# das_updated_v7.net
KiCad netlist of a schematic drawn in EAGLE
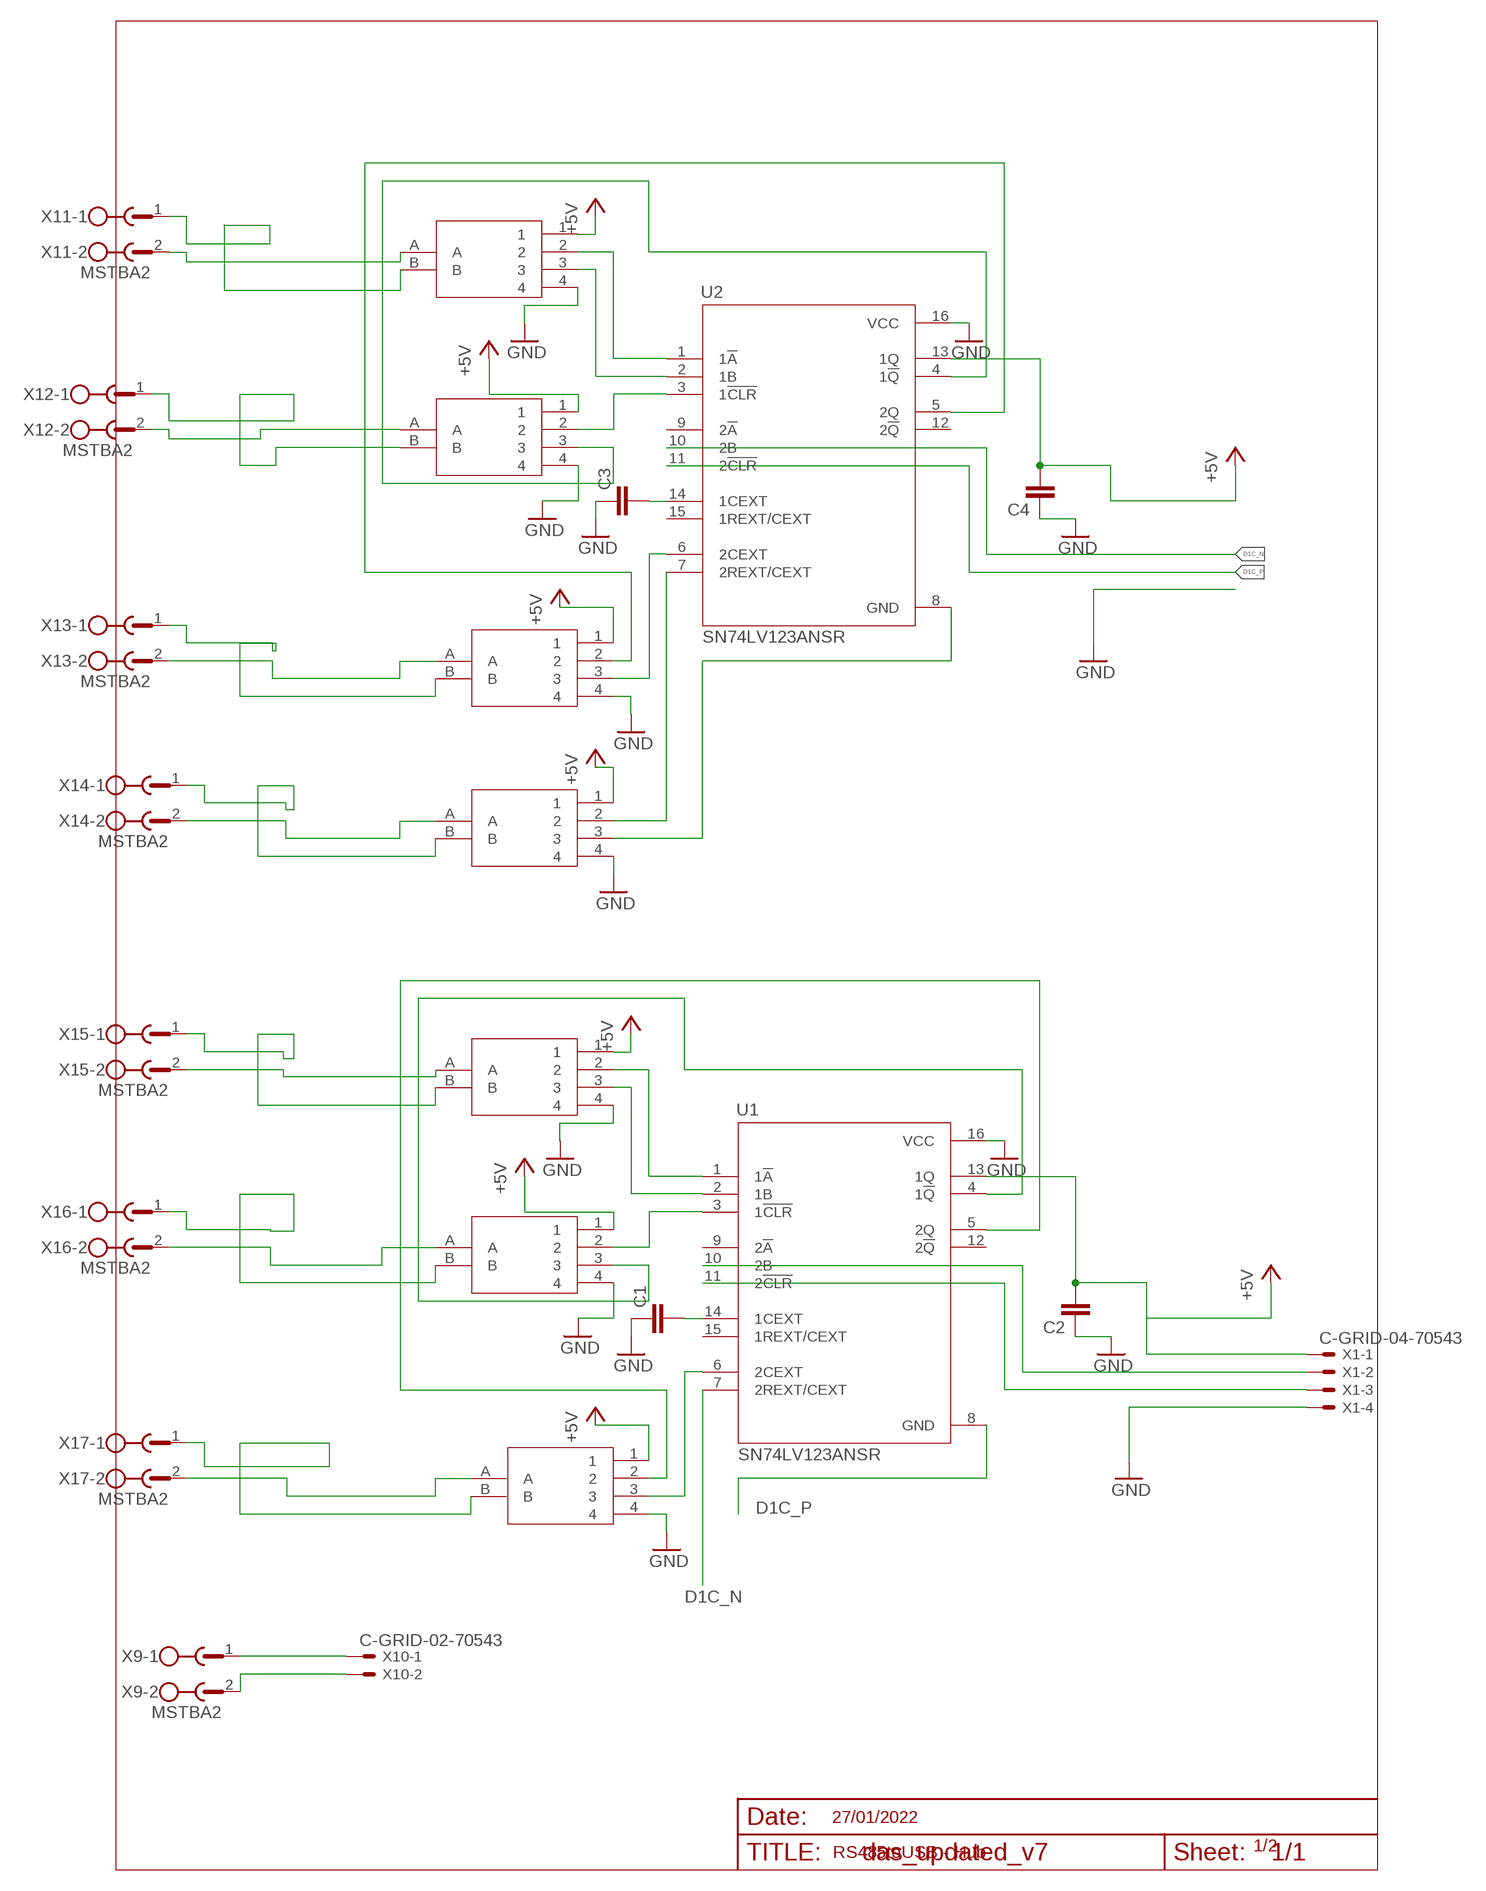
[diagram p0: schematic, sheet 1]

(export (version "E")
  (design (tool "Eeschema 10.0.6"))
  (components
    (comp (ref "C1")
      (value "C-EUC0603K")
      (footprint "eagle-import:C0603K")
      (libsource (lib "eagle-import") (part "C-EUC0603K"))
    )
    (comp (ref "C2")
      (value "C-EUC0603K")
      (footprint "eagle-import:C0603K")
      (libsource (lib "eagle-import") (part "C-EUC0603K"))
    )
    (comp (ref "C3")
      (value "C-EUC0603K")
      (footprint "eagle-import:C0603K")
      (libsource (lib "eagle-import") (part "C-EUC0603K"))
    )
    (comp (ref "C4")
      (value "C-EUC0603K")
      (footprint "eagle-import:C0603K")
      (libsource (lib "eagle-import") (part "C-EUC0603K"))
    )
    (comp (ref "U1")
      (value "SN74LV123ANSR")
      (footprint "eagle-import:SOIC127P780X200-16N")
      (fields (field (name "MF") "Texas Instruments"))
      (libsource (lib "eagle-import") (part "SN74LV123ANSR"))
    )
    (comp (ref "U2")
      (value "SN74LV123ANSR")
      (footprint "eagle-import:SOIC127P780X200-16N")
      (fields (field (name "MF") "Texas Instruments"))
      (libsource (lib "eagle-import") (part "SN74LV123ANSR"))
    )
    (comp (ref "USB2RS1")
      (value "USB2RS485")
      (footprint "eagle-import:USB2RS485")
      (libsource (lib "eagle-import") (part "USB2RS485"))
    )
    (comp (ref "USB2RS2")
      (value "USB2RS485")
      (footprint "eagle-import:USB2RS485")
      (libsource (lib "eagle-import") (part "USB2RS485"))
    )
    (comp (ref "USB2RS3")
      (value "USB2RS485")
      (footprint "eagle-import:USB2RS485")
      (libsource (lib "eagle-import") (part "USB2RS485"))
    )
    (comp (ref "USB2RS5")
      (value "USB2RS485")
      (footprint "eagle-import:USB2RS485")
      (libsource (lib "eagle-import") (part "USB2RS485"))
    )
    (comp (ref "USB2RS6")
      (value "USB2RS485")
      (footprint "eagle-import:USB2RS485")
      (libsource (lib "eagle-import") (part "USB2RS485"))
    )
    (comp (ref "USB2RS7")
      (value "USB2RS485")
      (footprint "eagle-import:USB2RS485")
      (libsource (lib "eagle-import") (part "USB2RS485"))
    )
    (comp (ref "USB2RS8")
      (value "USB2RS485")
      (footprint "eagle-import:USB2RS485")
      (libsource (lib "eagle-import") (part "USB2RS485"))
    )
    (comp (ref "X1")
      (value "C-GRID-04-70543")
      (footprint "eagle-import:70543-04")
      (fields (field (name "MF") "MOLEX"))
      (libsource (lib "eagle-import") (part "C-GRID-04-70543"))
    )
    (comp (ref "X9")
      (value "MSTBA2")
      (footprint "eagle-import:MSTBA2")
      (fields (field (name "MF") "FARNELL") (field (name "MPN") "1757242"))
      (libsource (lib "eagle-import") (part "MSTBA2"))
    )
    (comp (ref "X10")
      (value "C-GRID-02-70543")
      (footprint "eagle-import:70543-02")
      (fields (field (name "MF") "MOLEX"))
      (libsource (lib "eagle-import") (part "C-GRID-02-70543"))
    )
    (comp (ref "X11")
      (value "MSTBA2")
      (footprint "eagle-import:MSTBA2")
      (fields (field (name "MF") "FARNELL") (field (name "MPN") "1757242"))
      (libsource (lib "eagle-import") (part "MSTBA2"))
    )
    (comp (ref "X12")
      (value "MSTBA2")
      (footprint "eagle-import:MSTBA2")
      (fields (field (name "MF") "FARNELL") (field (name "MPN") "1757242"))
      (libsource (lib "eagle-import") (part "MSTBA2"))
    )
    (comp (ref "X13")
      (value "MSTBA2")
      (footprint "eagle-import:MSTBA2")
      (fields (field (name "MF") "FARNELL") (field (name "MPN") "1757242"))
      (libsource (lib "eagle-import") (part "MSTBA2"))
    )
    (comp (ref "X14")
      (value "MSTBA2")
      (footprint "eagle-import:MSTBA2")
      (fields (field (name "MF") "FARNELL") (field (name "MPN") "1757242"))
      (libsource (lib "eagle-import") (part "MSTBA2"))
    )
    (comp (ref "X15")
      (value "MSTBA2")
      (footprint "eagle-import:MSTBA2")
      (fields (field (name "MF") "FARNELL") (field (name "MPN") "1757242"))
      (libsource (lib "eagle-import") (part "MSTBA2"))
    )
    (comp (ref "X16")
      (value "MSTBA2")
      (footprint "eagle-import:MSTBA2")
      (fields (field (name "MF") "FARNELL") (field (name "MPN") "1757242"))
      (libsource (lib "eagle-import") (part "MSTBA2"))
    )
    (comp (ref "X17")
      (value "MSTBA2")
      (footprint "eagle-import:MSTBA2")
      (fields (field (name "MF") "FARNELL") (field (name "MPN") "1757242"))
      (libsource (lib "eagle-import") (part "MSTBA2"))
    )
  )
  (nets
    (net (code "1") (name "+5V") (class "Default")
      (node (ref "C2") (pin "2") (pinfunction "2_2") (pintype "passive"))
      (node (ref "C4") (pin "2") (pinfunction "2_2") (pintype "passive"))
      (node (ref "U1") (pin "13") (pinfunction "1Q_13") (pintype "output"))
      (node (ref "U2") (pin "13") (pinfunction "1Q_13") (pintype "output"))
      (node (ref "USB2RS1") (pin "1") (pinfunction "1_1") (pintype "bidirectional"))
      (node (ref "USB2RS2") (pin "1") (pinfunction "1_1") (pintype "bidirectional"))
      (node (ref "USB2RS3") (pin "1") (pinfunction "1_1") (pintype "bidirectional"))
      (node (ref "USB2RS5") (pin "1") (pinfunction "1_1") (pintype "bidirectional"))
      (node (ref "USB2RS6") (pin "1") (pinfunction "1_1") (pintype "bidirectional"))
      (node (ref "USB2RS7") (pin "1") (pinfunction "1_1") (pintype "bidirectional"))
      (node (ref "USB2RS8") (pin "1") (pinfunction "1_1") (pintype "bidirectional"))
      (node (ref "X1") (pin "1") (pinfunction "S_1") (pintype "passive"))
    )
    (net (code "2") (name "D1C_N") (class "Default")
      (node (ref "U1") (pin "7") (pinfunction "2REXT/CEXT_7") (pintype "bidirectional"))
      (node (ref "U2") (pin "10") (pinfunction "2B_10") (pintype "input"))
    )
    (net (code "3") (name "D1C_P") (class "Default")
      (node (ref "U1") (pin "8") (pinfunction "GND_8") (pintype "power_in"))
      (node (ref "U2") (pin "11") (pinfunction "2~{CLR}_11") (pintype "input"))
    )
    (net (code "4") (name "GND") (class "Default")
      (node (ref "C1") (pin "1") (pinfunction "1_1") (pintype "passive"))
      (node (ref "C2") (pin "1") (pinfunction "1_1") (pintype "passive"))
      (node (ref "C3") (pin "1") (pinfunction "1_1") (pintype "passive"))
      (node (ref "C4") (pin "1") (pinfunction "1_1") (pintype "passive"))
      (node (ref "U1") (pin "16") (pinfunction "VCC_16") (pintype "power_in"))
      (node (ref "U2") (pin "16") (pinfunction "VCC_16") (pintype "power_in"))
      (node (ref "USB2RS1") (pin "4") (pinfunction "4_4") (pintype "bidirectional"))
      (node (ref "USB2RS2") (pin "4") (pinfunction "4_4") (pintype "bidirectional"))
      (node (ref "USB2RS3") (pin "4") (pinfunction "4_4") (pintype "bidirectional"))
      (node (ref "USB2RS5") (pin "4") (pinfunction "4_4") (pintype "bidirectional"))
      (node (ref "USB2RS6") (pin "4") (pinfunction "4_4") (pintype "bidirectional"))
      (node (ref "USB2RS7") (pin "4") (pinfunction "4_4") (pintype "bidirectional"))
      (node (ref "USB2RS8") (pin "4") (pinfunction "4_4") (pintype "bidirectional"))
      (node (ref "X1") (pin "4") (pinfunction "S_4") (pintype "passive"))
    )
    (net (code "5") (name "Net-(U1-1B)") (class "Default")
      (node (ref "U1") (pin "2") (pinfunction "1B_2") (pintype "input"))
      (node (ref "USB2RS1") (pin "3") (pinfunction "3_3") (pintype "bidirectional"))
    )
    (net (code "6") (name "Net-(U1-1CEXT)") (class "Default")
      (node (ref "C1") (pin "2") (pinfunction "2_2") (pintype "passive"))
      (node (ref "U1") (pin "14") (pinfunction "1CEXT_14") (pintype "bidirectional"))
    )
    (net (code "7") (name "Net-(U1-1~{A})") (class "Default")
      (node (ref "U1") (pin "1") (pinfunction "1~{A}_1") (pintype "input"))
      (node (ref "USB2RS1") (pin "2") (pinfunction "2_2") (pintype "bidirectional"))
    )
    (net (code "8") (name "Net-(U1-1~{CLR})") (class "Default")
      (node (ref "U1") (pin "3") (pinfunction "1~{CLR}_3") (pintype "input"))
      (node (ref "USB2RS2") (pin "2") (pinfunction "2_2") (pintype "bidirectional"))
    )
    (net (code "9") (name "Net-(U1-1~{Q})") (class "Default")
      (node (ref "U1") (pin "4") (pinfunction "1~{Q}_4") (pintype "output"))
      (node (ref "USB2RS2") (pin "3") (pinfunction "3_3") (pintype "bidirectional"))
    )
    (net (code "10") (name "Net-(U1-2B)") (class "Default")
      (node (ref "U1") (pin "10") (pinfunction "2B_10") (pintype "input"))
      (node (ref "X1") (pin "2") (pinfunction "S_2") (pintype "passive"))
    )
    (net (code "11") (name "Net-(U1-2CEXT)") (class "Default")
      (node (ref "U1") (pin "6") (pinfunction "2CEXT_6") (pintype "bidirectional"))
      (node (ref "USB2RS3") (pin "3") (pinfunction "3_3") (pintype "bidirectional"))
    )
    (net (code "12") (name "Net-(U1-2Q)") (class "Default")
      (node (ref "U1") (pin "5") (pinfunction "2Q_5") (pintype "output"))
      (node (ref "USB2RS3") (pin "2") (pinfunction "2_2") (pintype "bidirectional"))
    )
    (net (code "13") (name "Net-(U1-2~{CLR})") (class "Default")
      (node (ref "U1") (pin "11") (pinfunction "2~{CLR}_11") (pintype "input"))
      (node (ref "X1") (pin "3") (pinfunction "S_3") (pintype "passive"))
    )
    (net (code "14") (name "Net-(U2-1B)") (class "Default")
      (node (ref "U2") (pin "2") (pinfunction "1B_2") (pintype "input"))
      (node (ref "USB2RS5") (pin "3") (pinfunction "3_3") (pintype "bidirectional"))
    )
    (net (code "15") (name "Net-(U2-1CEXT)") (class "Default")
      (node (ref "C3") (pin "2") (pinfunction "2_2") (pintype "passive"))
      (node (ref "U2") (pin "14") (pinfunction "1CEXT_14") (pintype "bidirectional"))
    )
    (net (code "16") (name "Net-(U2-1~{A})") (class "Default")
      (node (ref "U2") (pin "1") (pinfunction "1~{A}_1") (pintype "input"))
      (node (ref "USB2RS5") (pin "2") (pinfunction "2_2") (pintype "bidirectional"))
    )
    (net (code "17") (name "Net-(U2-1~{CLR})") (class "Default")
      (node (ref "U2") (pin "3") (pinfunction "1~{CLR}_3") (pintype "input"))
      (node (ref "USB2RS6") (pin "2") (pinfunction "2_2") (pintype "bidirectional"))
    )
    (net (code "18") (name "Net-(U2-1~{Q})") (class "Default")
      (node (ref "U2") (pin "4") (pinfunction "1~{Q}_4") (pintype "output"))
      (node (ref "USB2RS6") (pin "3") (pinfunction "3_3") (pintype "bidirectional"))
    )
    (net (code "19") (name "Net-(U2-2CEXT)") (class "Default")
      (node (ref "U2") (pin "6") (pinfunction "2CEXT_6") (pintype "bidirectional"))
      (node (ref "USB2RS7") (pin "3") (pinfunction "3_3") (pintype "bidirectional"))
    )
    (net (code "20") (name "Net-(U2-2Q)") (class "Default")
      (node (ref "U2") (pin "5") (pinfunction "2Q_5") (pintype "output"))
      (node (ref "USB2RS7") (pin "2") (pinfunction "2_2") (pintype "bidirectional"))
    )
    (net (code "21") (name "Net-(U2-2REXT{slash}CEXT)") (class "Default")
      (node (ref "U2") (pin "7") (pinfunction "2REXT/CEXT_7") (pintype "bidirectional"))
      (node (ref "USB2RS8") (pin "2") (pinfunction "2_2") (pintype "bidirectional"))
    )
    (net (code "22") (name "Net-(U2-GND)") (class "Default")
      (node (ref "U2") (pin "8") (pinfunction "GND_8") (pintype "power_in"))
      (node (ref "USB2RS8") (pin "3") (pinfunction "3_3") (pintype "bidirectional"))
    )
    (net (code "23") (name "Net-(USB2RS1-PadB)") (class "Default")
      (node (ref "USB2RS1") (pin "B") (pinfunction "B_B") (pintype "bidirectional"))
      (node (ref "X15") (pin "1") (pinfunction "1_1") (pintype "passive"))
    )
    (net (code "24") (name "Net-(USB2RS2-PadB)") (class "Default")
      (node (ref "USB2RS2") (pin "B") (pinfunction "B_B") (pintype "bidirectional"))
      (node (ref "X16") (pin "1") (pinfunction "1_1") (pintype "passive"))
    )
    (net (code "25") (name "Net-(USB2RS3-PadB)") (class "Default")
      (node (ref "USB2RS3") (pin "B") (pinfunction "B_B") (pintype "bidirectional"))
      (node (ref "X17") (pin "1") (pinfunction "1_1") (pintype "passive"))
    )
    (net (code "26") (name "Net-(USB2RS5-PadB)") (class "Default")
      (node (ref "USB2RS5") (pin "B") (pinfunction "B_B") (pintype "bidirectional"))
      (node (ref "X11") (pin "1") (pinfunction "1_1") (pintype "passive"))
    )
    (net (code "27") (name "Net-(USB2RS6-PadB)") (class "Default")
      (node (ref "USB2RS6") (pin "B") (pinfunction "B_B") (pintype "bidirectional"))
      (node (ref "X12") (pin "1") (pinfunction "1_1") (pintype "passive"))
    )
    (net (code "28") (name "Net-(USB2RS7-PadB)") (class "Default")
      (node (ref "USB2RS7") (pin "B") (pinfunction "B_B") (pintype "bidirectional"))
      (node (ref "X13") (pin "1") (pinfunction "1_1") (pintype "passive"))
    )
    (net (code "29") (name "Net-(USB2RS8-PadB)") (class "Default")
      (node (ref "USB2RS8") (pin "B") (pinfunction "B_B") (pintype "bidirectional"))
      (node (ref "X14") (pin "1") (pinfunction "1_1") (pintype "passive"))
    )
    (net (code "30") (name "Net-(X10A-S)") (class "Default")
      (node (ref "X10") (pin "1") (pinfunction "S_1") (pintype "passive"))
      (node (ref "X9") (pin "1") (pinfunction "1_1") (pintype "passive"))
    )
    (net (code "31") (name "Net-(X10B-S)") (class "Default")
      (node (ref "X10") (pin "2") (pinfunction "S_2") (pintype "passive"))
      (node (ref "X9") (pin "2") (pinfunction "1_2") (pintype "passive"))
    )
    (net (code "32") (name "Net-(X11B-1)") (class "Default")
      (node (ref "USB2RS5") (pin "A") (pinfunction "A_A") (pintype "bidirectional"))
      (node (ref "X11") (pin "2") (pinfunction "1_2") (pintype "passive"))
    )
    (net (code "33") (name "Net-(X12B-1)") (class "Default")
      (node (ref "USB2RS6") (pin "A") (pinfunction "A_A") (pintype "bidirectional"))
      (node (ref "X12") (pin "2") (pinfunction "1_2") (pintype "passive"))
    )
    (net (code "34") (name "Net-(X13B-1)") (class "Default")
      (node (ref "USB2RS7") (pin "A") (pinfunction "A_A") (pintype "bidirectional"))
      (node (ref "X13") (pin "2") (pinfunction "1_2") (pintype "passive"))
    )
    (net (code "35") (name "Net-(X14B-1)") (class "Default")
      (node (ref "USB2RS8") (pin "A") (pinfunction "A_A") (pintype "bidirectional"))
      (node (ref "X14") (pin "2") (pinfunction "1_2") (pintype "passive"))
    )
    (net (code "36") (name "Net-(X15B-1)") (class "Default")
      (node (ref "USB2RS1") (pin "A") (pinfunction "A_A") (pintype "bidirectional"))
      (node (ref "X15") (pin "2") (pinfunction "1_2") (pintype "passive"))
    )
    (net (code "37") (name "Net-(X16B-1)") (class "Default")
      (node (ref "USB2RS2") (pin "A") (pinfunction "A_A") (pintype "bidirectional"))
      (node (ref "X16") (pin "2") (pinfunction "1_2") (pintype "passive"))
    )
    (net (code "38") (name "Net-(X17B-1)") (class "Default")
      (node (ref "USB2RS3") (pin "A") (pinfunction "A_A") (pintype "bidirectional"))
      (node (ref "X17") (pin "2") (pinfunction "1_2") (pintype "passive"))
    )
    (net (code "39") (name "unconnected-(U1-1REXT{slash}CEXT-Pad15)") (class "Default")
      (node (ref "U1") (pin "15") (pinfunction "1REXT/CEXT_15") (pintype "bidirectional"))
    )
    (net (code "40") (name "unconnected-(U1-2~{A}-Pad9)") (class "Default")
      (node (ref "U1") (pin "9") (pinfunction "2~{A}_9") (pintype "input"))
    )
    (net (code "41") (name "unconnected-(U1-2~{Q}-Pad12)") (class "Default")
      (node (ref "U1") (pin "12") (pinfunction "2~{Q}_12") (pintype "output"))
    )
    (net (code "42") (name "unconnected-(U2-1REXT{slash}CEXT-Pad15)") (class "Default")
      (node (ref "U2") (pin "15") (pinfunction "1REXT/CEXT_15") (pintype "bidirectional"))
    )
    (net (code "43") (name "unconnected-(U2-2~{A}-Pad9)") (class "Default")
      (node (ref "U2") (pin "9") (pinfunction "2~{A}_9") (pintype "input"))
    )
    (net (code "44") (name "unconnected-(U2-2~{Q}-Pad12)") (class "Default")
      (node (ref "U2") (pin "12") (pinfunction "2~{Q}_12") (pintype "output"))
    )
  )
)
